# ELEC_GPS_Shield_v1_1.net
KiCad netlist of a schematic drawn in EAGLE
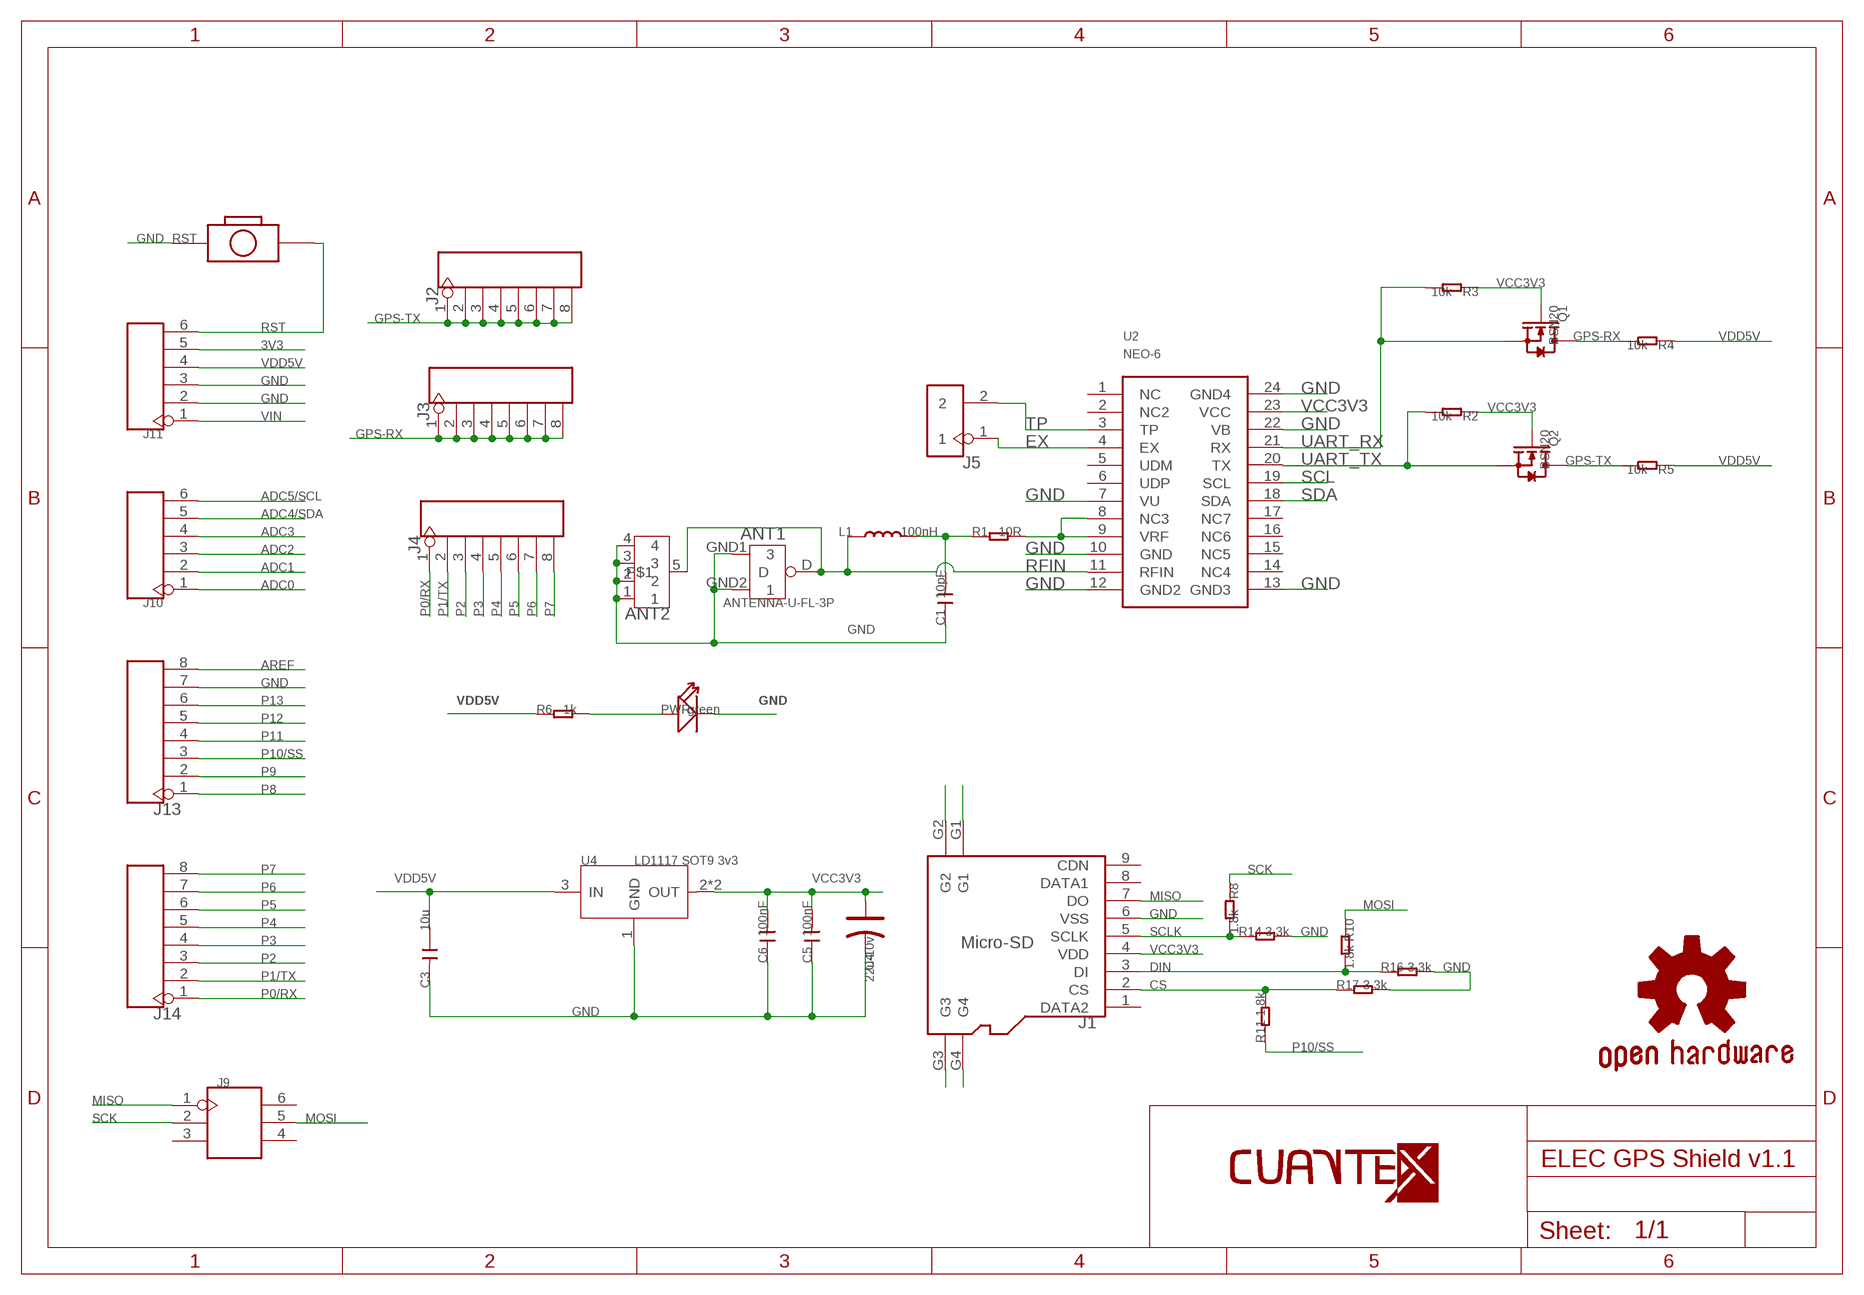
[diagram p0: schematic, sheet 1]

(export (version "E")
  (design (tool "Eeschema 10.0.6"))
  (components
    (comp (ref "ANT1")
      (value "ANTENNA-U-FL-3P")
      (footprint "eagle-import:3P-U-FL")
      (libsource (lib "eagle-import") (part "ANTENNA-U-FL-3P"))
    )
    (comp (ref "ANT2")
      (value "ANTENNA-SMA-IPX")
      (footprint "eagle-import:SMA-TO-IPX")
      (libsource (lib "eagle-import") (part "ANTENNA-SMA-IPX"))
    )
    (comp (ref "C1")
      (value "10pF")
      (footprint "eagle-import:C0603")
      (libsource (lib "eagle-import") (part "C-0603"))
    )
    (comp (ref "C3")
      (value "10u")
      (footprint "eagle-import:C0805")
      (libsource (lib "eagle-import") (part "C-0805"))
    )
    (comp (ref "C4")
      (value "22u-10v")
      (footprint "eagle-import:AVX-B")
      (libsource (lib "eagle-import") (part "CAP-AVX-B"))
    )
    (comp (ref "C5")
      (value "100nF")
      (footprint "eagle-import:C0603")
      (libsource (lib "eagle-import") (part "C-0603"))
    )
    (comp (ref "C6")
      (value "100nF")
      (footprint "eagle-import:C0603")
      (libsource (lib "eagle-import") (part "C-0603"))
    )
    (comp (ref "GOLD_ORB_SM1")
      (value "OSHWLOGO_GOLD_ORB_SM")
      (footprint "eagle-import:OSHW2")
      (libsource (lib "eagle-import") (part "OSHWLOGO_GOLD_ORB_SM"))
    )
    (comp (ref "J1")
      (value "Micro-SD")
      (footprint "eagle-import:9P-SMD-W_-RING")
      (libsource (lib "eagle-import") (part "HOLDER-MICROSD-9P"))
    )
    (comp (ref "J2")
      (value "HEADER-8P-65/35MIL")
      (footprint "eagle-import:8P-2.54-65_35MIL")
      (libsource (lib "eagle-import") (part "HEADER-8P-65/35MIL"))
    )
    (comp (ref "J3")
      (value "HEADER-8P-65/35MIL")
      (footprint "eagle-import:8P-2.54-65_35MIL")
      (libsource (lib "eagle-import") (part "HEADER-8P-65/35MIL"))
    )
    (comp (ref "J4")
      (value "HEADER-8P-65/35MIL")
      (footprint "eagle-import:8P-2.54-65_35MIL")
      (libsource (lib "eagle-import") (part "HEADER-8P-65/35MIL"))
    )
    (comp (ref "J5")
      (value "HEADER-2P-65/35MIL")
      (footprint "eagle-import:2P-2.54-65_35MIL")
      (libsource (lib "eagle-import") (part "HEADER-2P-65/35MIL"))
    )
    (comp (ref "J9")
      (value "HEADER-2X3P-65/35MIL")
      (footprint "eagle-import:2X3P-2.54-65_35MIL")
      (libsource (lib "eagle-import") (part "HEADER-2X3P-65/35MIL"))
    )
    (comp (ref "J10")
      (value "HEADER-6P-60/35MIL")
      (footprint "eagle-import:6P-2.54-60_35MIL")
      (libsource (lib "eagle-import") (part "HEADER-6P-60/35MIL"))
    )
    (comp (ref "J11")
      (value "HEADER-6P-60/35MIL")
      (footprint "eagle-import:6P-2.54-60_35MIL")
      (libsource (lib "eagle-import") (part "HEADER-6P-60/35MIL"))
    )
    (comp (ref "J13")
      (value "HEADER-8P-65/35MIL")
      (footprint "eagle-import:8P-2.54-65_35MIL")
      (libsource (lib "eagle-import") (part "HEADER-8P-65/35MIL"))
    )
    (comp (ref "J14")
      (value "HEADER-8P-65/35MIL")
      (footprint "eagle-import:8P-2.54-65_35MIL")
      (libsource (lib "eagle-import") (part "HEADER-8P-65/35MIL"))
    )
    (comp (ref "L1")
      (value "100nH")
      (footprint "eagle-import:L0603")
      (libsource (lib "eagle-import") (part "L'0603'"))
    )
    (comp (ref "PWR")
      (value "green")
      (footprint "eagle-import:LED-0603")
      (libsource (lib "eagle-import") (part "LED'0603'"))
    )
    (comp (ref "Q1")
      (value "BSN20")
      (footprint "eagle-import:SOT23")
      (libsource (lib "eagle-import") (part "MOSFET-N'SOT23'"))
    )
    (comp (ref "Q2")
      (value "BSN20")
      (footprint "eagle-import:SOT23")
      (libsource (lib "eagle-import") (part "MOSFET-N'SOT23'"))
    )
    (comp (ref "R1")
      (value "10R")
      (footprint "eagle-import:R0603")
      (libsource (lib "eagle-import") (part "R-0603"))
    )
    (comp (ref "R2")
      (value "10k")
      (footprint "eagle-import:R0603")
      (libsource (lib "eagle-import") (part "R-0603"))
    )
    (comp (ref "R3")
      (value "10k")
      (footprint "eagle-import:R0603")
      (libsource (lib "eagle-import") (part "R-0603"))
    )
    (comp (ref "R4")
      (value "10k")
      (footprint "eagle-import:R0603")
      (libsource (lib "eagle-import") (part "R-0603"))
    )
    (comp (ref "R5")
      (value "10k")
      (footprint "eagle-import:R0603")
      (libsource (lib "eagle-import") (part "R-0603"))
    )
    (comp (ref "R6")
      (value "1k")
      (footprint "eagle-import:R0603")
      (libsource (lib "eagle-import") (part "R-0603"))
    )
    (comp (ref "R8")
      (value "1.8k")
      (footprint "eagle-import:R0603")
      (libsource (lib "eagle-import") (part "R-0603"))
    )
    (comp (ref "R10")
      (value "1.8k")
      (footprint "eagle-import:R0603")
      (libsource (lib "eagle-import") (part "R-0603"))
    )
    (comp (ref "R11")
      (value "1.8k")
      (footprint "eagle-import:R0603")
      (libsource (lib "eagle-import") (part "R-0603"))
    )
    (comp (ref "R14")
      (value "3.3k")
      (footprint "eagle-import:R0603")
      (libsource (lib "eagle-import") (part "R-0603"))
    )
    (comp (ref "R16")
      (value "3.3k")
      (footprint "eagle-import:R0603")
      (libsource (lib "eagle-import") (part "R-0603"))
    )
    (comp (ref "R17")
      (value "3.3k")
      (footprint "eagle-import:R0603")
      (libsource (lib "eagle-import") (part "R-0603"))
    )
    (comp (ref "RST")
      (value "BOTTON-2P-90D")
      (footprint "eagle-import:2P-7.62X3.56-90D")
      (libsource (lib "eagle-import") (part "BOTTON-2P-90D"))
    )
    (comp (ref "U$1")
      (value "LOGO-BOT-40MM")
      (footprint "eagle-import:B-40")
      (libsource (lib "eagle-import") (part "LOGO-BOT-40MM"))
    )
    (comp (ref "U$3")
      (value "LOGO-TOP-20MM")
      (footprint "eagle-import:C-0")
      (libsource (lib "eagle-import") (part "LOGO-TOP-20MM"))
    )
    (comp (ref "U2")
      (value "NEO-6")
      (footprint "eagle-import:NEO-6")
      (libsource (lib "eagle-import") (part "NEO-6"))
    )
    (comp (ref "U4")
      (value "LD1117 SOT9 3v3")
      (footprint "eagle-import:SOT89")
      (libsource (lib "eagle-import") (part "LD1117'SOT89'"))
    )
  )
  (nets
    (net (code "1") (name "/3V3") (class "Default")
      (node (ref "J11") (pin "5") (pinfunction "5_5") (pintype "bidirectional"))
    )
    (net (code "2") (name "/ADC0") (class "Default")
      (node (ref "J10") (pin "1") (pinfunction "1_1") (pintype "bidirectional"))
    )
    (net (code "3") (name "/ADC1") (class "Default")
      (node (ref "J10") (pin "2") (pinfunction "2_2") (pintype "bidirectional"))
    )
    (net (code "4") (name "/ADC2") (class "Default")
      (node (ref "J10") (pin "3") (pinfunction "3_3") (pintype "bidirectional"))
    )
    (net (code "5") (name "/ADC3") (class "Default")
      (node (ref "J10") (pin "4") (pinfunction "4_4") (pintype "bidirectional"))
    )
    (net (code "6") (name "/ADC4{slash}SDA") (class "Default")
      (node (ref "J10") (pin "5") (pinfunction "5_5") (pintype "bidirectional"))
    )
    (net (code "7") (name "/ADC5{slash}SCL") (class "Default")
      (node (ref "J10") (pin "6") (pinfunction "6_6") (pintype "bidirectional"))
    )
    (net (code "8") (name "/AREF") (class "Default")
      (node (ref "J13") (pin "8") (pinfunction "8_8") (pintype "bidirectional"))
    )
    (net (code "9") (name "/CS") (class "Default")
      (node (ref "J1") (pin "2") (pinfunction "CS_2") (pintype "bidirectional"))
      (node (ref "R11") (pin "2") (pinfunction "2_2") (pintype "passive"))
      (node (ref "R17") (pin "1") (pinfunction "1_1") (pintype "passive"))
    )
    (net (code "10") (name "/DIN") (class "Default")
      (node (ref "J1") (pin "3") (pinfunction "DI_3") (pintype "bidirectional"))
      (node (ref "R10") (pin "2") (pinfunction "2_2") (pintype "passive"))
      (node (ref "R16") (pin "1") (pinfunction "1_1") (pintype "passive"))
    )
    (net (code "11") (name "/EX") (class "Default")
      (node (ref "J5") (pin "1") (pinfunction "1_1") (pintype "bidirectional"))
      (node (ref "U2") (pin "4") (pinfunction "EX_4") (pintype "bidirectional"))
    )
    (net (code "12") (name "/GND") (class "Default")
      (node (ref "ANT1") (pin "GND1") (pinfunction "3_GND1") (pintype "bidirectional"))
      (node (ref "ANT1") (pin "GND2") (pinfunction "1_GND2") (pintype "bidirectional"))
      (node (ref "ANT2") (pin "1") (pinfunction "1_1") (pintype "bidirectional"))
      (node (ref "ANT2") (pin "2") (pinfunction "2_2") (pintype "bidirectional"))
      (node (ref "ANT2") (pin "3") (pinfunction "3_3") (pintype "bidirectional"))
      (node (ref "ANT2") (pin "4") (pinfunction "4_4") (pintype "bidirectional"))
      (node (ref "C1") (pin "1") (pinfunction "1_1") (pintype "passive"))
      (node (ref "C3") (pin "2") (pinfunction "2_2") (pintype "passive"))
      (node (ref "C4") (pin "-") (pinfunction "-_-") (pintype "passive"))
      (node (ref "C5") (pin "1") (pinfunction "1_1") (pintype "passive"))
      (node (ref "C6") (pin "1") (pinfunction "1_1") (pintype "passive"))
      (node (ref "J1") (pin "6") (pinfunction "VSS_6") (pintype "bidirectional"))
      (node (ref "J11") (pin "2") (pinfunction "2_2") (pintype "bidirectional"))
      (node (ref "J11") (pin "3") (pinfunction "3_3") (pintype "bidirectional"))
      (node (ref "J13") (pin "7") (pinfunction "7_7") (pintype "bidirectional"))
      (node (ref "PWR") (pin "-") (pinfunction "-_-") (pintype "passive"))
      (node (ref "R14") (pin "2") (pinfunction "2_2") (pintype "passive"))
      (node (ref "R16") (pin "2") (pinfunction "2_2") (pintype "passive"))
      (node (ref "R17") (pin "2") (pinfunction "2_2") (pintype "passive"))
      (node (ref "RST") (pin "P$1") (pinfunction "1_P$1") (pintype "bidirectional"))
      (node (ref "U2") (pin "10") (pinfunction "GND_10") (pintype "bidirectional"))
      (node (ref "U2") (pin "12") (pinfunction "GND2_12") (pintype "bidirectional"))
      (node (ref "U2") (pin "13") (pinfunction "GND3_13") (pintype "bidirectional"))
      (node (ref "U2") (pin "22") (pinfunction "VB_22") (pintype "bidirectional"))
      (node (ref "U2") (pin "24") (pinfunction "GND4_24") (pintype "bidirectional"))
      (node (ref "U2") (pin "7") (pinfunction "VU_7") (pintype "bidirectional"))
      (node (ref "U4") (pin "1") (pinfunction "GND_1") (pintype "bidirectional"))
    )
    (net (code "13") (name "/GPS-RX") (class "Default")
      (node (ref "J3") (pin "1") (pinfunction "1_1") (pintype "bidirectional"))
      (node (ref "J3") (pin "2") (pinfunction "2_2") (pintype "bidirectional"))
      (node (ref "J3") (pin "3") (pinfunction "3_3") (pintype "bidirectional"))
      (node (ref "J3") (pin "4") (pinfunction "4_4") (pintype "bidirectional"))
      (node (ref "J3") (pin "5") (pinfunction "5_5") (pintype "bidirectional"))
      (node (ref "J3") (pin "6") (pinfunction "6_6") (pintype "bidirectional"))
      (node (ref "J3") (pin "7") (pinfunction "7_7") (pintype "bidirectional"))
      (node (ref "J3") (pin "8") (pinfunction "8_8") (pintype "bidirectional"))
      (node (ref "Q1") (pin "3") (pinfunction "D_3") (pintype "passive"))
      (node (ref "R4") (pin "2") (pinfunction "2_2") (pintype "passive"))
    )
    (net (code "14") (name "/GPS-TX") (class "Default")
      (node (ref "J2") (pin "1") (pinfunction "1_1") (pintype "bidirectional"))
      (node (ref "J2") (pin "2") (pinfunction "2_2") (pintype "bidirectional"))
      (node (ref "J2") (pin "3") (pinfunction "3_3") (pintype "bidirectional"))
      (node (ref "J2") (pin "4") (pinfunction "4_4") (pintype "bidirectional"))
      (node (ref "J2") (pin "5") (pinfunction "5_5") (pintype "bidirectional"))
      (node (ref "J2") (pin "6") (pinfunction "6_6") (pintype "bidirectional"))
      (node (ref "J2") (pin "7") (pinfunction "7_7") (pintype "bidirectional"))
      (node (ref "J2") (pin "8") (pinfunction "8_8") (pintype "bidirectional"))
      (node (ref "Q2") (pin "3") (pinfunction "D_3") (pintype "passive"))
      (node (ref "R5") (pin "2") (pinfunction "2_2") (pintype "passive"))
    )
    (net (code "15") (name "/MISO") (class "Default")
      (node (ref "J1") (pin "7") (pinfunction "DO_7") (pintype "bidirectional"))
      (node (ref "J9") (pin "1") (pinfunction "1_1") (pintype "bidirectional"))
    )
    (net (code "16") (name "/MOSI") (class "Default")
      (node (ref "J9") (pin "5") (pinfunction "5_5") (pintype "bidirectional"))
      (node (ref "R10") (pin "1") (pinfunction "1_1") (pintype "passive"))
    )
    (net (code "17") (name "/P0{slash}RX") (class "Default")
      (node (ref "J14") (pin "1") (pinfunction "1_1") (pintype "bidirectional"))
      (node (ref "J4") (pin "1") (pinfunction "1_1") (pintype "bidirectional"))
    )
    (net (code "18") (name "/P1{slash}TX") (class "Default")
      (node (ref "J14") (pin "2") (pinfunction "2_2") (pintype "bidirectional"))
      (node (ref "J4") (pin "2") (pinfunction "2_2") (pintype "bidirectional"))
    )
    (net (code "19") (name "/P2") (class "Default")
      (node (ref "J14") (pin "3") (pinfunction "3_3") (pintype "bidirectional"))
      (node (ref "J4") (pin "3") (pinfunction "3_3") (pintype "bidirectional"))
    )
    (net (code "20") (name "/P3") (class "Default")
      (node (ref "J14") (pin "4") (pinfunction "4_4") (pintype "bidirectional"))
      (node (ref "J4") (pin "4") (pinfunction "4_4") (pintype "bidirectional"))
    )
    (net (code "21") (name "/P4") (class "Default")
      (node (ref "J14") (pin "5") (pinfunction "5_5") (pintype "bidirectional"))
      (node (ref "J4") (pin "5") (pinfunction "5_5") (pintype "bidirectional"))
    )
    (net (code "22") (name "/P5") (class "Default")
      (node (ref "J14") (pin "6") (pinfunction "6_6") (pintype "bidirectional"))
      (node (ref "J4") (pin "6") (pinfunction "6_6") (pintype "bidirectional"))
    )
    (net (code "23") (name "/P6") (class "Default")
      (node (ref "J14") (pin "7") (pinfunction "7_7") (pintype "bidirectional"))
      (node (ref "J4") (pin "7") (pinfunction "7_7") (pintype "bidirectional"))
    )
    (net (code "24") (name "/P7") (class "Default")
      (node (ref "J14") (pin "8") (pinfunction "8_8") (pintype "bidirectional"))
      (node (ref "J4") (pin "8") (pinfunction "8_8") (pintype "bidirectional"))
    )
    (net (code "25") (name "/P8") (class "Default")
      (node (ref "J13") (pin "1") (pinfunction "1_1") (pintype "bidirectional"))
    )
    (net (code "26") (name "/P9") (class "Default")
      (node (ref "J13") (pin "2") (pinfunction "2_2") (pintype "bidirectional"))
    )
    (net (code "27") (name "/P10{slash}SS") (class "Default")
      (node (ref "J13") (pin "3") (pinfunction "3_3") (pintype "bidirectional"))
      (node (ref "R11") (pin "1") (pinfunction "1_1") (pintype "passive"))
    )
    (net (code "28") (name "/P11") (class "Default")
      (node (ref "J13") (pin "4") (pinfunction "4_4") (pintype "bidirectional"))
    )
    (net (code "29") (name "/P12") (class "Default")
      (node (ref "J13") (pin "5") (pinfunction "5_5") (pintype "bidirectional"))
    )
    (net (code "30") (name "/P13") (class "Default")
      (node (ref "J13") (pin "6") (pinfunction "6_6") (pintype "bidirectional"))
    )
    (net (code "31") (name "/RFIN") (class "Default")
      (node (ref "ANT1") (pin "D") (pinfunction "D_D") (pintype "bidirectional"))
      (node (ref "ANT2") (pin "5") (pinfunction "P$1_5") (pintype "bidirectional"))
      (node (ref "L1") (pin "1") (pinfunction "1_1") (pintype "passive"))
      (node (ref "U2") (pin "11") (pinfunction "RFIN_11") (pintype "bidirectional"))
    )
    (net (code "32") (name "/RST") (class "Default")
      (node (ref "J11") (pin "6") (pinfunction "6_6") (pintype "bidirectional"))
      (node (ref "RST") (pin "P$2") (pinfunction "2_P$2") (pintype "bidirectional"))
    )
    (net (code "33") (name "/SCK") (class "Default")
      (node (ref "J9") (pin "2") (pinfunction "2_2") (pintype "bidirectional"))
      (node (ref "R8") (pin "1") (pinfunction "1_1") (pintype "passive"))
    )
    (net (code "34") (name "/SCL") (class "Default")
      (node (ref "U2") (pin "19") (pinfunction "SCL_19") (pintype "bidirectional"))
    )
    (net (code "35") (name "/SCLK") (class "Default")
      (node (ref "J1") (pin "5") (pinfunction "SCLK_5") (pintype "bidirectional"))
      (node (ref "R14") (pin "1") (pinfunction "1_1") (pintype "passive"))
      (node (ref "R8") (pin "2") (pinfunction "2_2") (pintype "passive"))
    )
    (net (code "36") (name "/SDA") (class "Default")
      (node (ref "U2") (pin "18") (pinfunction "SDA_18") (pintype "bidirectional"))
    )
    (net (code "37") (name "/TP") (class "Default")
      (node (ref "J5") (pin "2") (pinfunction "2_2") (pintype "bidirectional"))
      (node (ref "U2") (pin "3") (pinfunction "TP_3") (pintype "bidirectional"))
    )
    (net (code "38") (name "/UART_RX") (class "Default")
      (node (ref "Q1") (pin "2") (pinfunction "S_2") (pintype "passive"))
      (node (ref "R3") (pin "2") (pinfunction "2_2") (pintype "passive"))
      (node (ref "U2") (pin "21") (pinfunction "RX_21") (pintype "bidirectional"))
    )
    (net (code "39") (name "/UART_TX") (class "Default")
      (node (ref "Q2") (pin "2") (pinfunction "S_2") (pintype "passive"))
      (node (ref "R2") (pin "2") (pinfunction "2_2") (pintype "passive"))
      (node (ref "U2") (pin "20") (pinfunction "TX_20") (pintype "bidirectional"))
    )
    (net (code "40") (name "/VCC3V3") (class "Default")
      (node (ref "C4") (pin "+") (pinfunction "+_+") (pintype "passive"))
      (node (ref "C5") (pin "2") (pinfunction "2_2") (pintype "passive"))
      (node (ref "C6") (pin "2") (pinfunction "2_2") (pintype "passive"))
      (node (ref "J1") (pin "4") (pinfunction "VDD_4") (pintype "bidirectional"))
      (node (ref "Q1") (pin "1") (pinfunction "G_1") (pintype "passive"))
      (node (ref "Q2") (pin "1") (pinfunction "G_1") (pintype "passive"))
      (node (ref "R2") (pin "1") (pinfunction "1_1") (pintype "passive"))
      (node (ref "R3") (pin "1") (pinfunction "1_1") (pintype "passive"))
      (node (ref "U2") (pin "23") (pinfunction "VCC_23") (pintype "bidirectional"))
      (node (ref "U4") (pin "2") (pinfunction "OUT_2") (pintype "bidirectional"))
      (node (ref "U4") (pin "4") (pinfunction "OUT_4") (pintype "bidirectional"))
    )
    (net (code "41") (name "/VDD5V") (class "Default")
      (node (ref "C3") (pin "1") (pinfunction "1_1") (pintype "passive"))
      (node (ref "J11") (pin "4") (pinfunction "4_4") (pintype "bidirectional"))
      (node (ref "R4") (pin "1") (pinfunction "1_1") (pintype "passive"))
      (node (ref "R5") (pin "1") (pinfunction "1_1") (pintype "passive"))
      (node (ref "R6") (pin "1") (pinfunction "1_1") (pintype "passive"))
      (node (ref "U4") (pin "3") (pinfunction "IN_3") (pintype "bidirectional"))
    )
    (net (code "42") (name "/VIN") (class "Default")
      (node (ref "J11") (pin "1") (pinfunction "1_1") (pintype "bidirectional"))
    )
    (net (code "43") (name "Net-(C1-Pad2)") (class "Default")
      (node (ref "C1") (pin "2") (pinfunction "2_2") (pintype "passive"))
      (node (ref "L1") (pin "2") (pinfunction "2_2") (pintype "passive"))
      (node (ref "R1") (pin "1") (pinfunction "1_1") (pintype "passive"))
    )
    (net (code "44") (name "Net-(PWR-Pad+)") (class "Default")
      (node (ref "PWR") (pin "+") (pinfunction "+_+") (pintype "passive"))
      (node (ref "R6") (pin "2") (pinfunction "2_2") (pintype "passive"))
    )
    (net (code "45") (name "Net-(U2-NC3)") (class "Default")
      (node (ref "R1") (pin "2") (pinfunction "2_2") (pintype "passive"))
      (node (ref "U2") (pin "8") (pinfunction "NC3_8") (pintype "bidirectional"))
      (node (ref "U2") (pin "9") (pinfunction "VRF_9") (pintype "bidirectional"))
    )
    (net (code "46") (name "unconnected-(J1-CDN-Pad9)") (class "Default")
      (node (ref "J1") (pin "9") (pinfunction "CDN_9") (pintype "bidirectional"))
    )
    (net (code "47") (name "unconnected-(J1-DATA1-Pad8)") (class "Default")
      (node (ref "J1") (pin "8") (pinfunction "DATA1_8") (pintype "bidirectional"))
    )
    (net (code "48") (name "unconnected-(J1-DATA2-Pad1)") (class "Default")
      (node (ref "J1") (pin "1") (pinfunction "DATA2_1") (pintype "bidirectional"))
    )
    (net (code "49") (name "unconnected-(J1-PadG1)") (class "Default")
      (node (ref "J1") (pin "G1") (pinfunction "G1_G1") (pintype "bidirectional"))
    )
    (net (code "50") (name "unconnected-(J1-PadG2)") (class "Default")
      (node (ref "J1") (pin "G2") (pinfunction "G2_G2") (pintype "bidirectional"))
    )
    (net (code "51") (name "unconnected-(J1-PadG3)") (class "Default")
      (node (ref "J1") (pin "G3") (pinfunction "G3_G3") (pintype "bidirectional"))
    )
    (net (code "52") (name "unconnected-(J1-PadG4)") (class "Default")
      (node (ref "J1") (pin "G4") (pinfunction "G4_G4") (pintype "bidirectional"))
    )
    (net (code "53") (name "unconnected-(J9-Pad3)") (class "Default")
      (node (ref "J9") (pin "3") (pinfunction "3_3") (pintype "bidirectional"))
    )
    (net (code "54") (name "unconnected-(J9-Pad4)") (class "Default")
      (node (ref "J9") (pin "4") (pinfunction "4_4") (pintype "bidirectional"))
    )
    (net (code "55") (name "unconnected-(J9-Pad6)") (class "Default")
      (node (ref "J9") (pin "6") (pinfunction "6_6") (pintype "bidirectional"))
    )
    (net (code "56") (name "unconnected-(U2-NC-Pad1)") (class "Default")
      (node (ref "U2") (pin "1") (pinfunction "NC_1") (pintype "bidirectional"))
    )
    (net (code "57") (name "unconnected-(U2-NC2-Pad2)") (class "Default")
      (node (ref "U2") (pin "2") (pinfunction "NC2_2") (pintype "bidirectional"))
    )
    (net (code "58") (name "unconnected-(U2-NC4-Pad14)") (class "Default")
      (node (ref "U2") (pin "14") (pinfunction "NC4_14") (pintype "bidirectional"))
    )
    (net (code "59") (name "unconnected-(U2-NC5-Pad15)") (class "Default")
      (node (ref "U2") (pin "15") (pinfunction "NC5_15") (pintype "bidirectional"))
    )
    (net (code "60") (name "unconnected-(U2-NC6-Pad16)") (class "Default")
      (node (ref "U2") (pin "16") (pinfunction "NC6_16") (pintype "bidirectional"))
    )
    (net (code "61") (name "unconnected-(U2-NC7-Pad17)") (class "Default")
      (node (ref "U2") (pin "17") (pinfunction "NC7_17") (pintype "bidirectional"))
    )
    (net (code "62") (name "unconnected-(U2-UDM-Pad5)") (class "Default")
      (node (ref "U2") (pin "5") (pinfunction "UDM_5") (pintype "bidirectional"))
    )
    (net (code "63") (name "unconnected-(U2-UDP-Pad6)") (class "Default")
      (node (ref "U2") (pin "6") (pinfunction "UDP_6") (pintype "bidirectional"))
    )
  )
)
